# controller3.net
KiCad netlist of a schematic drawn in EAGLE
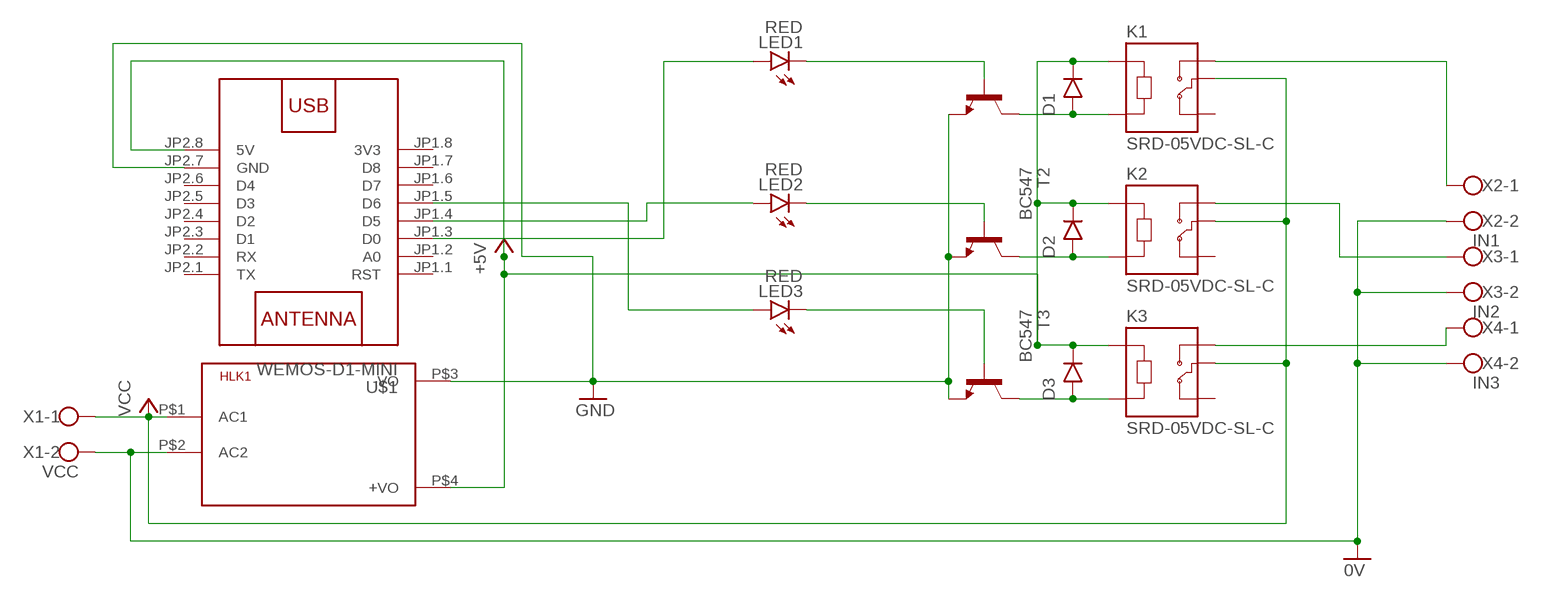
[diagram p0: schematic, sheet 1]

(export (version "E")
  (design (tool "Eeschema 10.0.6"))
  (components
    (comp (ref "D1")
      (value "1N4001")
      (footprint "eagle-import:DO41-10")
      (libsource (lib "eagle-import") (part "1N4001"))
    )
    (comp (ref "D2")
      (value "1N4001")
      (footprint "eagle-import:DO41-10")
      (libsource (lib "eagle-import") (part "1N4001"))
    )
    (comp (ref "D3")
      (value "1N4001")
      (footprint "eagle-import:DO41-10")
      (libsource (lib "eagle-import") (part "1N4001"))
    )
    (comp (ref "HLK1")
      (value "HLK-PM013W")
      (footprint "eagle-import:HLK-PM01")
      (libsource (lib "eagle-import") (part "HLK-PM013W"))
    )
    (comp (ref "K1")
      (value "SRD-05VDC-SL-C")
      (footprint "eagle-import:RELAY_SRD-05VDC-SL-C")
      (fields (field (name "MF") "Songle Relay"))
      (libsource (lib "eagle-import") (part "SRD-05VDC-SL-C"))
    )
    (comp (ref "K2")
      (value "SRD-05VDC-SL-C")
      (footprint "eagle-import:RELAY_SRD-05VDC-SL-C")
      (fields (field (name "MF") "Songle Relay"))
      (libsource (lib "eagle-import") (part "SRD-05VDC-SL-C"))
    )
    (comp (ref "K3")
      (value "SRD-05VDC-SL-C")
      (footprint "eagle-import:RELAY_SRD-05VDC-SL-C")
      (fields (field (name "MF") "Songle Relay"))
      (libsource (lib "eagle-import") (part "SRD-05VDC-SL-C"))
    )
    (comp (ref "LED1")
      (value "RED")
      (footprint "eagle-import:LED3MM")
      (libsource (lib "eagle-import") (part "LED3MM"))
    )
    (comp (ref "LED2")
      (value "RED")
      (footprint "eagle-import:LED3MM")
      (libsource (lib "eagle-import") (part "LED3MM"))
    )
    (comp (ref "LED3")
      (value "RED")
      (footprint "eagle-import:LED3MM")
      (libsource (lib "eagle-import") (part "LED3MM"))
    )
    (comp (ref "T1")
      (value "BC547")
      (footprint "eagle-import:TO92")
      (libsource (lib "eagle-import") (part "BC547"))
    )
    (comp (ref "T2")
      (value "BC547")
      (footprint "eagle-import:TO92")
      (libsource (lib "eagle-import") (part "BC547"))
    )
    (comp (ref "T3")
      (value "BC547")
      (footprint "eagle-import:TO92")
      (libsource (lib "eagle-import") (part "BC547"))
    )
    (comp (ref "U$1")
      (value "WEMOS-D1-MINI")
      (footprint "eagle-import:WEMOS-D1-MINI")
      (libsource (lib "eagle-import") (part "WEMOS-D1-MINI"))
    )
    (comp (ref "X1")
      (value "VCC")
      (footprint "eagle-import:W237-102")
      (fields (field (name "MPN") "237-102"))
      (libsource (lib "eagle-import") (part "W237-102"))
    )
    (comp (ref "X2")
      (value "IN1")
      (footprint "eagle-import:W237-102")
      (fields (field (name "MPN") "237-102"))
      (libsource (lib "eagle-import") (part "W237-102"))
    )
    (comp (ref "X3")
      (value "IN2")
      (footprint "eagle-import:W237-102")
      (fields (field (name "MPN") "237-102"))
      (libsource (lib "eagle-import") (part "W237-102"))
    )
    (comp (ref "X4")
      (value "IN3")
      (footprint "eagle-import:W237-102")
      (fields (field (name "MPN") "237-102"))
      (libsource (lib "eagle-import") (part "W237-102"))
    )
  )
  (nets
    (net (code "1") (name "+5V") (class "Default")
      (node (ref "D1") (pin "C") (pinfunction "CATHODE_C") (pintype "passive"))
      (node (ref "D2") (pin "C") (pinfunction "CATHODE_C") (pintype "passive"))
      (node (ref "D3") (pin "C") (pinfunction "CATHODE_C") (pintype "passive"))
      (node (ref "HLK1") (pin "P$4") (pinfunction "+VO_P$4") (pintype "bidirectional"))
      (node (ref "K1") (pin "A1") (pinfunction "A1_A1") (pintype "passive"))
      (node (ref "K2") (pin "A1") (pinfunction "A1_A1") (pintype "passive"))
      (node (ref "K3") (pin "A1") (pinfunction "A1_A1") (pintype "passive"))
      (node (ref "U$1") (pin "JP2.8") (pinfunction "5V_JP2.8") (pintype "power_in"))
    )
    (net (code "2") (name "/3V3") (class "Default")
      (node (ref "U$1") (pin "JP1.8") (pinfunction "3V3_JP1.8") (pintype "power_in"))
    )
    (net (code "3") (name "0V") (class "Default")
      (node (ref "HLK1") (pin "P$2") (pinfunction "AC2_P$2") (pintype "bidirectional"))
      (node (ref "X1") (pin "2") (pinfunction "KL_2") (pintype "passive"))
      (node (ref "X2") (pin "2") (pinfunction "KL_2") (pintype "passive"))
      (node (ref "X3") (pin "2") (pinfunction "KL_2") (pintype "passive"))
      (node (ref "X4") (pin "2") (pinfunction "KL_2") (pintype "passive"))
    )
    (net (code "4") (name "GND") (class "Default")
      (node (ref "HLK1") (pin "P$3") (pinfunction "-VO_P$3") (pintype "bidirectional"))
      (node (ref "T1") (pin "1") (pinfunction "E_1") (pintype "passive"))
      (node (ref "T2") (pin "1") (pinfunction "E_1") (pintype "passive"))
      (node (ref "T3") (pin "1") (pinfunction "E_1") (pintype "passive"))
      (node (ref "U$1") (pin "JP2.7") (pinfunction "GND_JP2.7") (pintype "power_in"))
    )
    (net (code "5") (name "Net-(D1-ANODE)") (class "Default")
      (node (ref "D1") (pin "A") (pinfunction "ANODE_A") (pintype "passive"))
      (node (ref "K1") (pin "A2") (pinfunction "A2_A2") (pintype "passive"))
      (node (ref "T1") (pin "3") (pinfunction "C_3") (pintype "passive"))
    )
    (net (code "6") (name "Net-(D2-ANODE)") (class "Default")
      (node (ref "D2") (pin "A") (pinfunction "ANODE_A") (pintype "passive"))
      (node (ref "K2") (pin "A2") (pinfunction "A2_A2") (pintype "passive"))
      (node (ref "T2") (pin "3") (pinfunction "C_3") (pintype "passive"))
    )
    (net (code "7") (name "Net-(D3-ANODE)") (class "Default")
      (node (ref "D3") (pin "A") (pinfunction "ANODE_A") (pintype "passive"))
      (node (ref "K3") (pin "A2") (pinfunction "A2_A2") (pintype "passive"))
      (node (ref "T3") (pin "3") (pinfunction "C_3") (pintype "passive"))
    )
    (net (code "8") (name "Net-(LED1-C)") (class "Default")
      (node (ref "LED1") (pin "K") (pinfunction "C_K") (pintype "passive"))
      (node (ref "T1") (pin "2") (pinfunction "B_2") (pintype "passive"))
    )
    (net (code "9") (name "Net-(LED2-C)") (class "Default")
      (node (ref "LED2") (pin "K") (pinfunction "C_K") (pintype "passive"))
      (node (ref "T2") (pin "2") (pinfunction "B_2") (pintype "passive"))
    )
    (net (code "10") (name "Net-(LED3-C)") (class "Default")
      (node (ref "LED3") (pin "K") (pinfunction "C_K") (pintype "passive"))
      (node (ref "T3") (pin "2") (pinfunction "B_2") (pintype "passive"))
    )
    (net (code "11") (name "Net-(U$1-D0)") (class "Default")
      (node (ref "LED1") (pin "A") (pinfunction "A_A") (pintype "passive"))
      (node (ref "U$1") (pin "JP1.3") (pinfunction "D0_JP1.3") (pintype "bidirectional"))
    )
    (net (code "12") (name "Net-(U$1-D5)") (class "Default")
      (node (ref "LED2") (pin "A") (pinfunction "A_A") (pintype "passive"))
      (node (ref "U$1") (pin "JP1.4") (pinfunction "D5_JP1.4") (pintype "bidirectional"))
    )
    (net (code "13") (name "Net-(U$1-D6)") (class "Default")
      (node (ref "LED3") (pin "A") (pinfunction "A_A") (pintype "passive"))
      (node (ref "U$1") (pin "JP1.5") (pinfunction "D6_JP1.5") (pintype "bidirectional"))
    )
    (net (code "14") (name "Net-(X2A-KL)") (class "Default")
      (node (ref "K1") (pin "NO") (pinfunction "NO_NO") (pintype "passive"))
      (node (ref "X2") (pin "1") (pinfunction "KL_1") (pintype "passive"))
    )
    (net (code "15") (name "Net-(X3A-KL)") (class "Default")
      (node (ref "K2") (pin "NO") (pinfunction "NO_NO") (pintype "passive"))
      (node (ref "X3") (pin "1") (pinfunction "KL_1") (pintype "passive"))
    )
    (net (code "16") (name "Net-(X4A-KL)") (class "Default")
      (node (ref "K3") (pin "NO") (pinfunction "NO_NO") (pintype "passive"))
      (node (ref "X4") (pin "1") (pinfunction "KL_1") (pintype "passive"))
    )
    (net (code "17") (name "VCC") (class "Default")
      (node (ref "HLK1") (pin "P$1") (pinfunction "AC1_P$1") (pintype "bidirectional"))
      (node (ref "K1") (pin "COM") (pinfunction "COM_COM") (pintype "passive"))
      (node (ref "K2") (pin "COM") (pinfunction "COM_COM") (pintype "passive"))
      (node (ref "K3") (pin "COM") (pinfunction "COM_COM") (pintype "passive"))
      (node (ref "X1") (pin "1") (pinfunction "KL_1") (pintype "passive"))
    )
    (net (code "18") (name "unconnected-(K1-PadNC)") (class "Default")
      (node (ref "K1") (pin "NC") (pinfunction "NC_NC") (pintype "passive"))
    )
    (net (code "19") (name "unconnected-(K2-PadNC)") (class "Default")
      (node (ref "K2") (pin "NC") (pinfunction "NC_NC") (pintype "passive"))
    )
    (net (code "20") (name "unconnected-(K3-PadNC)") (class "Default")
      (node (ref "K3") (pin "NC") (pinfunction "NC_NC") (pintype "passive"))
    )
    (net (code "21") (name "unconnected-(U$1-A0-PadJP1.2)") (class "Default")
      (node (ref "U$1") (pin "JP1.2") (pinfunction "A0_JP1.2") (pintype "bidirectional"))
    )
    (net (code "22") (name "unconnected-(U$1-D1-PadJP2.3)") (class "Default")
      (node (ref "U$1") (pin "JP2.3") (pinfunction "D1_JP2.3") (pintype "bidirectional"))
    )
    (net (code "23") (name "unconnected-(U$1-D2-PadJP2.4)") (class "Default")
      (node (ref "U$1") (pin "JP2.4") (pinfunction "D2_JP2.4") (pintype "bidirectional"))
    )
    (net (code "24") (name "unconnected-(U$1-D3-PadJP2.5)") (class "Default")
      (node (ref "U$1") (pin "JP2.5") (pinfunction "D3_JP2.5") (pintype "bidirectional"))
    )
    (net (code "25") (name "unconnected-(U$1-D4-PadJP2.6)") (class "Default")
      (node (ref "U$1") (pin "JP2.6") (pinfunction "D4_JP2.6") (pintype "bidirectional"))
    )
    (net (code "26") (name "unconnected-(U$1-D7-PadJP1.6)") (class "Default")
      (node (ref "U$1") (pin "JP1.6") (pinfunction "D7_JP1.6") (pintype "bidirectional"))
    )
    (net (code "27") (name "unconnected-(U$1-D8-PadJP1.7)") (class "Default")
      (node (ref "U$1") (pin "JP1.7") (pinfunction "D8_JP1.7") (pintype "bidirectional"))
    )
    (net (code "28") (name "unconnected-(U$1-RST-PadJP1.1)") (class "Default")
      (node (ref "U$1") (pin "JP1.1") (pinfunction "RST_JP1.1") (pintype "bidirectional"))
    )
    (net (code "29") (name "unconnected-(U$1-RX-PadJP2.2)") (class "Default")
      (node (ref "U$1") (pin "JP2.2") (pinfunction "RX_JP2.2") (pintype "bidirectional"))
    )
    (net (code "30") (name "unconnected-(U$1-TX-PadJP2.1)") (class "Default")
      (node (ref "U$1") (pin "JP2.1") (pinfunction "TX_JP2.1") (pintype "bidirectional"))
    )
  )
)
